# SPO2_New.net
KiCad netlist of a schematic drawn in EAGLE
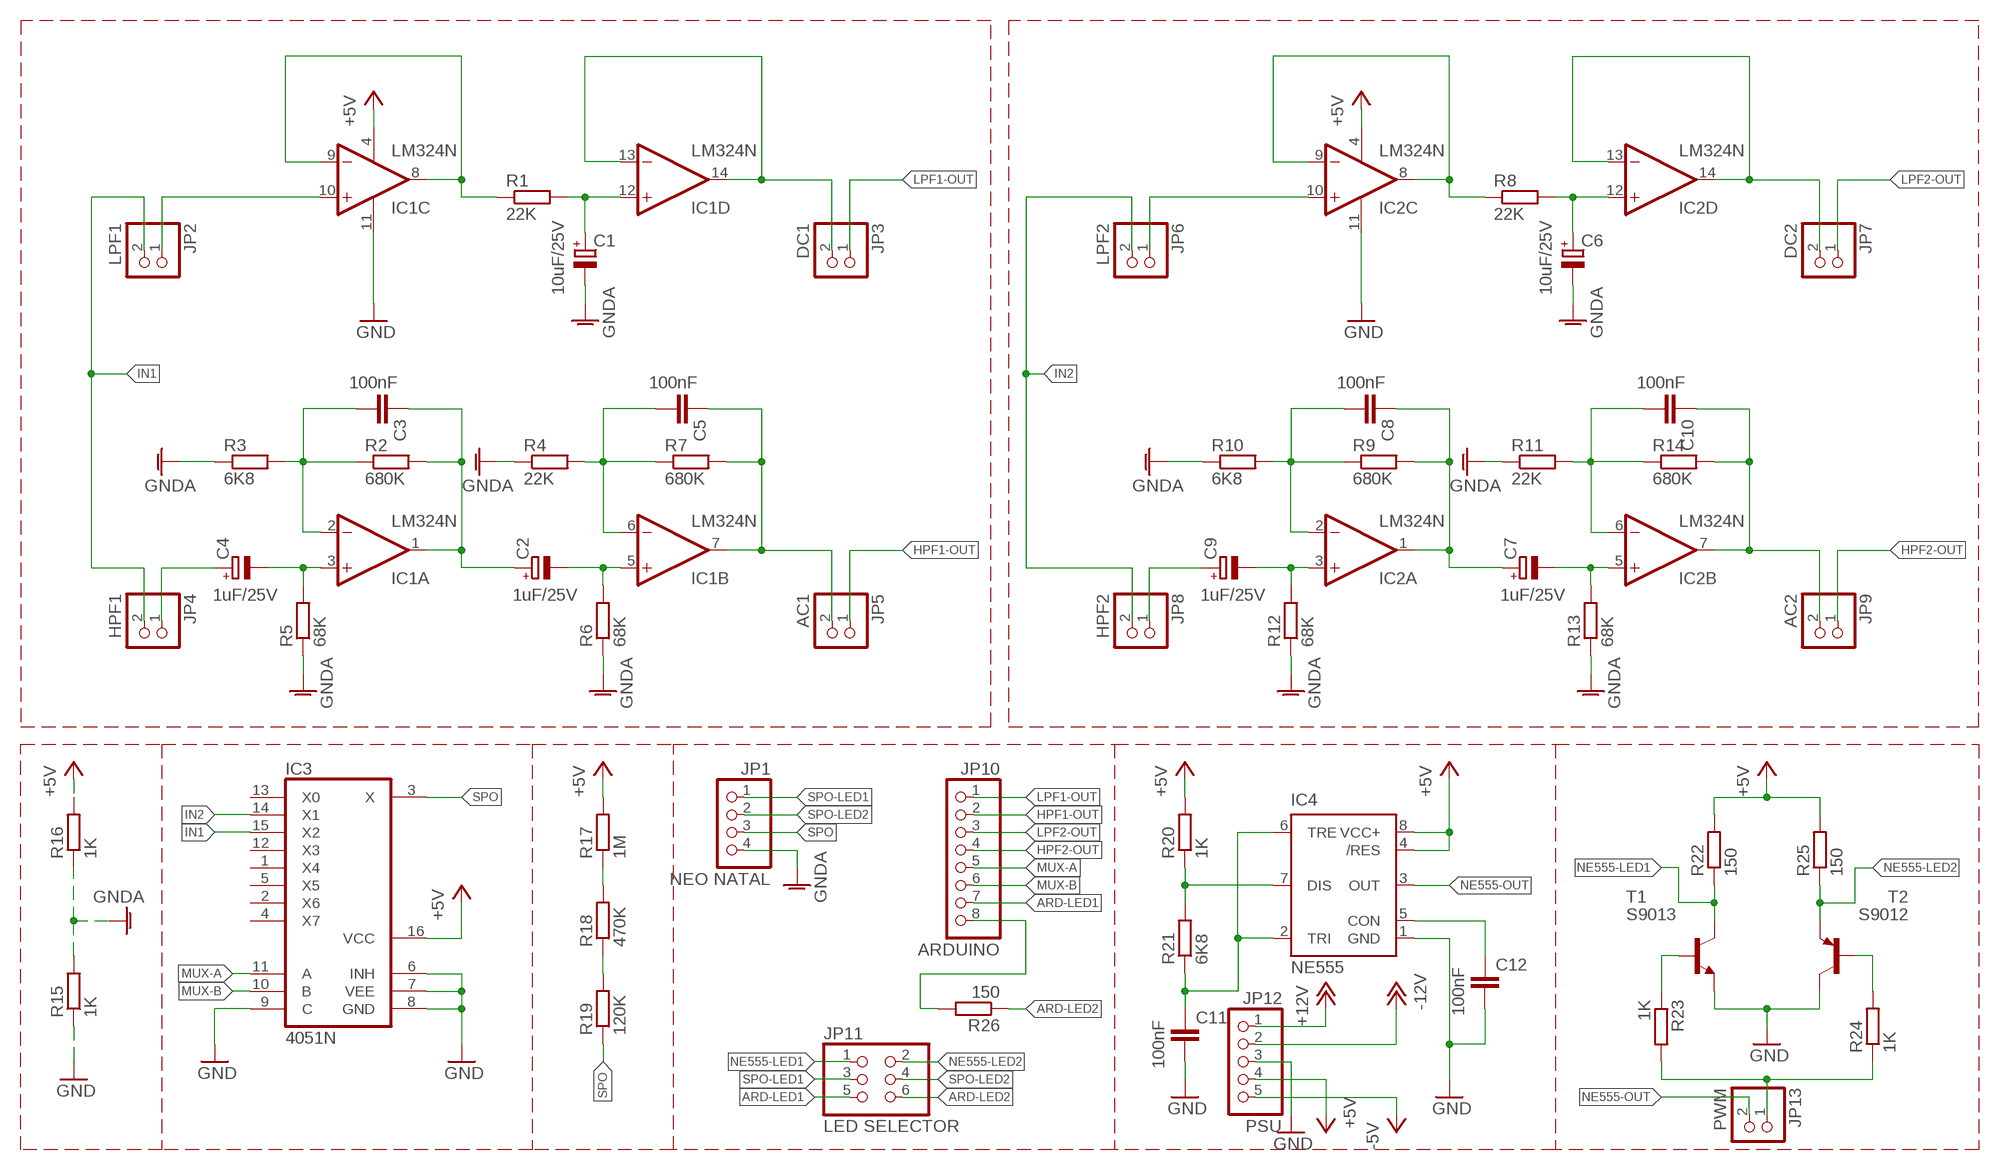
[diagram p0: schematic, sheet 1]

(export (version "E")
  (design (tool "Eeschema 10.0.6"))
  (components
    (comp (ref "C1")
      (value "10uF/25V")
      (footprint "eagle-import:E2,5-6")
      (libsource (lib "eagle-import") (part "CPOL-EUE2.5-6"))
    )
    (comp (ref "C2")
      (value "1uF/25V")
      (footprint "eagle-import:E2,5-6")
      (libsource (lib "eagle-import") (part "CPOL-EUE2.5-6"))
    )
    (comp (ref "C3")
      (value "100nF")
      (footprint "eagle-import:C050-025X075")
      (libsource (lib "eagle-import") (part "C-EU050-025X075"))
    )
    (comp (ref "C4")
      (value "1uF/25V")
      (footprint "eagle-import:E2,5-6")
      (libsource (lib "eagle-import") (part "CPOL-EUE2.5-6"))
    )
    (comp (ref "C5")
      (value "100nF")
      (footprint "eagle-import:C050-025X075")
      (libsource (lib "eagle-import") (part "C-EU050-025X075"))
    )
    (comp (ref "C6")
      (value "10uF/25V")
      (footprint "eagle-import:E2,5-6")
      (libsource (lib "eagle-import") (part "CPOL-EUE2.5-6"))
    )
    (comp (ref "C7")
      (value "1uF/25V")
      (footprint "eagle-import:E2,5-6")
      (libsource (lib "eagle-import") (part "CPOL-EUE2.5-6"))
    )
    (comp (ref "C8")
      (value "100nF")
      (footprint "eagle-import:C050-025X075")
      (libsource (lib "eagle-import") (part "C-EU050-025X075"))
    )
    (comp (ref "C9")
      (value "1uF/25V")
      (footprint "eagle-import:E2,5-6")
      (libsource (lib "eagle-import") (part "CPOL-EUE2.5-6"))
    )
    (comp (ref "C10")
      (value "100nF")
      (footprint "eagle-import:C050-025X075")
      (libsource (lib "eagle-import") (part "C-EU050-025X075"))
    )
    (comp (ref "C11")
      (value "100nF")
      (footprint "eagle-import:C050-025X075")
      (libsource (lib "eagle-import") (part "C-EU050-025X075"))
    )
    (comp (ref "C12")
      (value "100nF")
      (footprint "eagle-import:C050-025X075")
      (libsource (lib "eagle-import") (part "C-EU050-025X075"))
    )
    (comp (ref "IC1")
      (value "LM324N")
      (footprint "eagle-import:DIL14")
      (libsource (lib "eagle-import") (part "LM324N"))
    )
    (comp (ref "IC2")
      (value "LM324N")
      (footprint "eagle-import:DIL14")
      (libsource (lib "eagle-import") (part "LM324N"))
    )
    (comp (ref "IC3")
      (value "4051N")
      (footprint "eagle-import:DIL16")
      (libsource (lib "eagle-import") (part "4051N"))
    )
    (comp (ref "IC4")
      (value "NE555")
      (footprint "eagle-import:DIL-08")
      (fields (field (name "MF") "Arrow Electronics") (field (name "MPN") "NE555N"))
      (libsource (lib "eagle-import") (part "NE555"))
    )
    (comp (ref "JP1")
      (value "NEO NATAL")
      (footprint "eagle-import:1X04")
      (libsource (lib "eagle-import") (part "PINHD-1X4"))
    )
    (comp (ref "JP2")
      (value "LPF1")
      (footprint "eagle-import:1X02")
      (libsource (lib "eagle-import") (part "PINHD-1X2"))
    )
    (comp (ref "JP3")
      (value "DC1")
      (footprint "eagle-import:1X02")
      (libsource (lib "eagle-import") (part "PINHD-1X2"))
    )
    (comp (ref "JP4")
      (value "HPF1")
      (footprint "eagle-import:1X02")
      (libsource (lib "eagle-import") (part "PINHD-1X2"))
    )
    (comp (ref "JP5")
      (value "AC1")
      (footprint "eagle-import:1X02")
      (libsource (lib "eagle-import") (part "PINHD-1X2"))
    )
    (comp (ref "JP6")
      (value "LPF2")
      (footprint "eagle-import:1X02")
      (libsource (lib "eagle-import") (part "PINHD-1X2"))
    )
    (comp (ref "JP7")
      (value "DC2")
      (footprint "eagle-import:1X02")
      (libsource (lib "eagle-import") (part "PINHD-1X2"))
    )
    (comp (ref "JP8")
      (value "HPF2")
      (footprint "eagle-import:1X02")
      (libsource (lib "eagle-import") (part "PINHD-1X2"))
    )
    (comp (ref "JP9")
      (value "AC2")
      (footprint "eagle-import:1X02")
      (libsource (lib "eagle-import") (part "PINHD-1X2"))
    )
    (comp (ref "JP10")
      (value "ARDUINO")
      (footprint "eagle-import:1X08")
      (libsource (lib "eagle-import") (part "PINHD-1X8"))
    )
    (comp (ref "JP11")
      (value "LED SELECTOR")
      (footprint "eagle-import:2X03")
      (libsource (lib "eagle-import") (part "PINHD-2X3"))
    )
    (comp (ref "JP12")
      (value "PSU")
      (footprint "eagle-import:1X05")
      (libsource (lib "eagle-import") (part "PINHD-1X5{dblquote}"))
    )
    (comp (ref "JP13")
      (value "PWM")
      (footprint "eagle-import:1X02")
      (libsource (lib "eagle-import") (part "PINHD-1X2"))
    )
    (comp (ref "R1")
      (value "22K")
      (footprint "eagle-import:0207_7")
      (libsource (lib "eagle-import") (part "R-EU_0207/7"))
    )
    (comp (ref "R2")
      (value "680K")
      (footprint "eagle-import:0207_7")
      (libsource (lib "eagle-import") (part "R-EU_0207/7"))
    )
    (comp (ref "R3")
      (value "6K8")
      (footprint "eagle-import:0207_7")
      (libsource (lib "eagle-import") (part "R-EU_0207/7"))
    )
    (comp (ref "R4")
      (value "22K")
      (footprint "eagle-import:0207_7")
      (libsource (lib "eagle-import") (part "R-EU_0207/7"))
    )
    (comp (ref "R5")
      (value "68K")
      (footprint "eagle-import:0207_7")
      (libsource (lib "eagle-import") (part "R-EU_0207/7"))
    )
    (comp (ref "R6")
      (value "68K")
      (footprint "eagle-import:0207_7")
      (libsource (lib "eagle-import") (part "R-EU_0207/7"))
    )
    (comp (ref "R7")
      (value "680K")
      (footprint "eagle-import:0207_7")
      (libsource (lib "eagle-import") (part "R-EU_0207/7"))
    )
    (comp (ref "R8")
      (value "22K")
      (footprint "eagle-import:0207_7")
      (libsource (lib "eagle-import") (part "R-EU_0207/7"))
    )
    (comp (ref "R9")
      (value "680K")
      (footprint "eagle-import:0207_7")
      (libsource (lib "eagle-import") (part "R-EU_0207/7"))
    )
    (comp (ref "R10")
      (value "6K8")
      (footprint "eagle-import:0207_7")
      (libsource (lib "eagle-import") (part "R-EU_0207/7"))
    )
    (comp (ref "R11")
      (value "22K")
      (footprint "eagle-import:0207_7")
      (libsource (lib "eagle-import") (part "R-EU_0207/7"))
    )
    (comp (ref "R12")
      (value "68K")
      (footprint "eagle-import:0207_7")
      (libsource (lib "eagle-import") (part "R-EU_0207/7"))
    )
    (comp (ref "R13")
      (value "68K")
      (footprint "eagle-import:0207_7")
      (libsource (lib "eagle-import") (part "R-EU_0207/7"))
    )
    (comp (ref "R14")
      (value "680K")
      (footprint "eagle-import:0207_7")
      (libsource (lib "eagle-import") (part "R-EU_0207/7"))
    )
    (comp (ref "R15")
      (value "1K")
      (footprint "eagle-import:0207_7")
      (libsource (lib "eagle-import") (part "R-EU_0207/7"))
    )
    (comp (ref "R16")
      (value "1K")
      (footprint "eagle-import:0207_7")
      (libsource (lib "eagle-import") (part "R-EU_0207/7"))
    )
    (comp (ref "R17")
      (value "1M")
      (footprint "eagle-import:0207_7")
      (libsource (lib "eagle-import") (part "R-EU_0207/7"))
    )
    (comp (ref "R18")
      (value "470K")
      (footprint "eagle-import:0207_7")
      (libsource (lib "eagle-import") (part "R-EU_0207/7"))
    )
    (comp (ref "R19")
      (value "120K")
      (footprint "eagle-import:0207_7")
      (libsource (lib "eagle-import") (part "R-EU_0207/7"))
    )
    (comp (ref "R20")
      (value "1K")
      (footprint "eagle-import:0207_7")
      (libsource (lib "eagle-import") (part "R-EU_0207/7"))
    )
    (comp (ref "R21")
      (value "6K8")
      (footprint "eagle-import:0207_7")
      (libsource (lib "eagle-import") (part "R-EU_0207/7"))
    )
    (comp (ref "R22")
      (value "150")
      (footprint "eagle-import:0207_7")
      (libsource (lib "eagle-import") (part "R-EU_0207/7"))
    )
    (comp (ref "R23")
      (value "1K")
      (footprint "eagle-import:0207_7")
      (libsource (lib "eagle-import") (part "R-EU_0207/7"))
    )
    (comp (ref "R24")
      (value "1K")
      (footprint "eagle-import:0207_7")
      (libsource (lib "eagle-import") (part "R-EU_0207/7"))
    )
    (comp (ref "R25")
      (value "150")
      (footprint "eagle-import:0207_7")
      (libsource (lib "eagle-import") (part "R-EU_0207/7"))
    )
    (comp (ref "R26")
      (value "150")
      (footprint "eagle-import:0207_7")
      (libsource (lib "eagle-import") (part "R-EU_0207/7"))
    )
    (comp (ref "T1")
      (value "S9013")
      (footprint "eagle-import:TO92-EBC")
      (libsource (lib "eagle-import") (part "-NPN-TO92-EBCBC319"))
    )
    (comp (ref "T2")
      (value "S9012")
      (footprint "eagle-import:TO92-EBC")
      (libsource (lib "eagle-import") (part "-PNP-TO92-EBCBC327-16"))
    )
  )
  (nets
    (net (code "1") (name "+5V") (class "Default")
      (node (ref "IC1") (pin "4") (pinfunction "V+_4") (pintype "power_in"))
      (node (ref "IC2") (pin "4") (pinfunction "V+_4") (pintype "power_in"))
      (node (ref "IC3") (pin "16") (pinfunction "VCC_16") (pintype "power_in"))
      (node (ref "IC4") (pin "4") (pinfunction "/RES_4") (pintype "input"))
      (node (ref "IC4") (pin "8") (pinfunction "VCC+_8") (pintype "power_in"))
      (node (ref "JP12") (pin "4") (pinfunction "4_4") (pintype "passive"))
      (node (ref "R16") (pin "2") (pinfunction "2_2") (pintype "passive"))
      (node (ref "R17") (pin "2") (pinfunction "2_2") (pintype "passive"))
      (node (ref "R20") (pin "2") (pinfunction "2_2") (pintype "passive"))
      (node (ref "R22") (pin "2") (pinfunction "2_2") (pintype "passive"))
      (node (ref "R25") (pin "2") (pinfunction "2_2") (pintype "passive"))
    )
    (net (code "2") (name "+12V") (class "Default")
      (node (ref "JP12") (pin "1") (pinfunction "1_1") (pintype "passive"))
    )
    (net (code "3") (name "-5V") (class "Default")
      (node (ref "JP12") (pin "5") (pinfunction "5_5") (pintype "passive"))
    )
    (net (code "4") (name "-12V") (class "Default")
      (node (ref "JP12") (pin "2") (pinfunction "2_2") (pintype "passive"))
    )
    (net (code "5") (name "ARD-LED1") (class "Default")
      (node (ref "JP10") (pin "7") (pinfunction "7_7") (pintype "passive"))
      (node (ref "JP11") (pin "5") (pinfunction "5_5") (pintype "passive"))
    )
    (net (code "6") (name "ARD-LED2") (class "Default")
      (node (ref "JP11") (pin "6") (pinfunction "6_6") (pintype "passive"))
      (node (ref "R26") (pin "1") (pinfunction "1_1") (pintype "passive"))
    )
    (net (code "7") (name "GND") (class "Default")
      (node (ref "C11") (pin "2") (pinfunction "2_2") (pintype "passive"))
      (node (ref "C12") (pin "2") (pinfunction "2_2") (pintype "passive"))
      (node (ref "IC1") (pin "11") (pinfunction "V-_11") (pintype "power_in"))
      (node (ref "IC2") (pin "11") (pinfunction "V-_11") (pintype "power_in"))
      (node (ref "IC3") (pin "6") (pinfunction "INH_6") (pintype "input"))
      (node (ref "IC3") (pin "7") (pinfunction "VEE_7") (pintype "power_in"))
      (node (ref "IC3") (pin "8") (pinfunction "GND_8") (pintype "power_in"))
      (node (ref "IC3") (pin "9") (pinfunction "C_9") (pintype "input"))
      (node (ref "IC4") (pin "1") (pinfunction "GND_1") (pintype "power_in"))
      (node (ref "JP12") (pin "3") (pinfunction "3_3") (pintype "passive"))
      (node (ref "R15") (pin "1") (pinfunction "1_1") (pintype "passive"))
      (node (ref "T1") (pin "E") (pinfunction "E_E") (pintype "passive"))
      (node (ref "T2") (pin "C") (pinfunction "C_C") (pintype "passive"))
    )
    (net (code "8") (name "GNDA") (class "Default")
      (node (ref "C1") (pin "-") (pinfunction "-_-") (pintype "passive"))
      (node (ref "C6") (pin "-") (pinfunction "-_-") (pintype "passive"))
      (node (ref "JP1") (pin "4") (pinfunction "4_4") (pintype "passive"))
      (node (ref "R10") (pin "1") (pinfunction "1_1") (pintype "passive"))
      (node (ref "R11") (pin "1") (pinfunction "1_1") (pintype "passive"))
      (node (ref "R12") (pin "1") (pinfunction "1_1") (pintype "passive"))
      (node (ref "R13") (pin "1") (pinfunction "1_1") (pintype "passive"))
      (node (ref "R15") (pin "2") (pinfunction "2_2") (pintype "passive"))
      (node (ref "R16") (pin "1") (pinfunction "1_1") (pintype "passive"))
      (node (ref "R3") (pin "1") (pinfunction "1_1") (pintype "passive"))
      (node (ref "R4") (pin "1") (pinfunction "1_1") (pintype "passive"))
      (node (ref "R5") (pin "1") (pinfunction "1_1") (pintype "passive"))
      (node (ref "R6") (pin "1") (pinfunction "1_1") (pintype "passive"))
    )
    (net (code "9") (name "HPF1-OUT") (class "Default")
      (node (ref "JP10") (pin "2") (pinfunction "2_2") (pintype "passive"))
      (node (ref "JP5") (pin "1") (pinfunction "1_1") (pintype "passive"))
    )
    (net (code "10") (name "HPF2-OUT") (class "Default")
      (node (ref "JP10") (pin "4") (pinfunction "4_4") (pintype "passive"))
      (node (ref "JP9") (pin "1") (pinfunction "1_1") (pintype "passive"))
    )
    (net (code "11") (name "IN1") (class "Default")
      (node (ref "IC3") (pin "15") (pinfunction "X2_15") (pintype "bidirectional"))
      (node (ref "JP2") (pin "2") (pinfunction "2_2") (pintype "passive"))
      (node (ref "JP4") (pin "2") (pinfunction "2_2") (pintype "passive"))
    )
    (net (code "12") (name "IN2") (class "Default")
      (node (ref "IC3") (pin "14") (pinfunction "X1_14") (pintype "bidirectional"))
      (node (ref "JP6") (pin "2") (pinfunction "2_2") (pintype "passive"))
      (node (ref "JP8") (pin "2") (pinfunction "2_2") (pintype "passive"))
    )
    (net (code "13") (name "LPF1-OUT") (class "Default")
      (node (ref "JP10") (pin "1") (pinfunction "1_1") (pintype "passive"))
      (node (ref "JP3") (pin "1") (pinfunction "1_1") (pintype "passive"))
    )
    (net (code "14") (name "LPF2-OUT") (class "Default")
      (node (ref "JP10") (pin "3") (pinfunction "3_3") (pintype "passive"))
      (node (ref "JP7") (pin "1") (pinfunction "1_1") (pintype "passive"))
    )
    (net (code "15") (name "MUX-A") (class "Default")
      (node (ref "IC3") (pin "11") (pinfunction "A_11") (pintype "input"))
      (node (ref "JP10") (pin "5") (pinfunction "5_5") (pintype "passive"))
    )
    (net (code "16") (name "MUX-B") (class "Default")
      (node (ref "IC3") (pin "10") (pinfunction "B_10") (pintype "input"))
      (node (ref "JP10") (pin "6") (pinfunction "6_6") (pintype "passive"))
    )
    (net (code "17") (name "NE555-LED1") (class "Default")
      (node (ref "JP11") (pin "1") (pinfunction "1_1") (pintype "passive"))
      (node (ref "R22") (pin "1") (pinfunction "1_1") (pintype "passive"))
      (node (ref "T1") (pin "C") (pinfunction "C_C") (pintype "passive"))
    )
    (net (code "18") (name "NE555-LED2") (class "Default")
      (node (ref "JP11") (pin "2") (pinfunction "2_2") (pintype "passive"))
      (node (ref "R25") (pin "1") (pinfunction "1_1") (pintype "passive"))
      (node (ref "T2") (pin "E") (pinfunction "E_E") (pintype "passive"))
    )
    (net (code "19") (name "NE555-OUT") (class "Default")
      (node (ref "IC4") (pin "3") (pinfunction "OUT_3") (pintype "output"))
      (node (ref "JP13") (pin "2") (pinfunction "2_2") (pintype "passive"))
    )
    (net (code "20") (name "Net-(C4-Pad+)") (class "Default")
      (node (ref "C4") (pin "+") (pinfunction "+_+") (pintype "passive"))
      (node (ref "JP4") (pin "1") (pinfunction "1_1") (pintype "passive"))
    )
    (net (code "21") (name "Net-(C9-Pad+)") (class "Default")
      (node (ref "C9") (pin "+") (pinfunction "+_+") (pintype "passive"))
      (node (ref "JP8") (pin "1") (pinfunction "1_1") (pintype "passive"))
    )
    (net (code "22") (name "Net-(IC1A-+IN)") (class "Default")
      (node (ref "C4") (pin "-") (pinfunction "-_-") (pintype "passive"))
      (node (ref "IC1") (pin "3") (pinfunction "+IN_3") (pintype "input"))
      (node (ref "R5") (pin "2") (pinfunction "2_2") (pintype "passive"))
    )
    (net (code "23") (name "Net-(IC1A--IN)") (class "Default")
      (node (ref "C3") (pin "2") (pinfunction "2_2") (pintype "passive"))
      (node (ref "IC1") (pin "2") (pinfunction "-IN_2") (pintype "input"))
      (node (ref "R2") (pin "1") (pinfunction "1_1") (pintype "passive"))
      (node (ref "R3") (pin "2") (pinfunction "2_2") (pintype "passive"))
    )
    (net (code "24") (name "Net-(IC1A-OUT)") (class "Default")
      (node (ref "C2") (pin "+") (pinfunction "+_+") (pintype "passive"))
      (node (ref "C3") (pin "1") (pinfunction "1_1") (pintype "passive"))
      (node (ref "IC1") (pin "1") (pinfunction "OUT_1") (pintype "output"))
      (node (ref "R2") (pin "2") (pinfunction "2_2") (pintype "passive"))
    )
    (net (code "25") (name "Net-(IC1B-+IN)") (class "Default")
      (node (ref "C2") (pin "-") (pinfunction "-_-") (pintype "passive"))
      (node (ref "IC1") (pin "5") (pinfunction "+IN_5") (pintype "input"))
      (node (ref "R6") (pin "2") (pinfunction "2_2") (pintype "passive"))
    )
    (net (code "26") (name "Net-(IC1B--IN)") (class "Default")
      (node (ref "C5") (pin "2") (pinfunction "2_2") (pintype "passive"))
      (node (ref "IC1") (pin "6") (pinfunction "-IN_6") (pintype "input"))
      (node (ref "R4") (pin "2") (pinfunction "2_2") (pintype "passive"))
      (node (ref "R7") (pin "1") (pinfunction "1_1") (pintype "passive"))
    )
    (net (code "27") (name "Net-(IC1B-OUT)") (class "Default")
      (node (ref "C5") (pin "1") (pinfunction "1_1") (pintype "passive"))
      (node (ref "IC1") (pin "7") (pinfunction "OUT_7") (pintype "output"))
      (node (ref "JP5") (pin "2") (pinfunction "2_2") (pintype "passive"))
      (node (ref "R7") (pin "2") (pinfunction "2_2") (pintype "passive"))
    )
    (net (code "28") (name "Net-(IC1C-+IN)") (class "Default")
      (node (ref "IC1") (pin "10") (pinfunction "+IN_10") (pintype "input"))
      (node (ref "JP2") (pin "1") (pinfunction "1_1") (pintype "passive"))
    )
    (net (code "29") (name "Net-(IC1C--IN)") (class "Default")
      (node (ref "IC1") (pin "8") (pinfunction "OUT_8") (pintype "output"))
      (node (ref "IC1") (pin "9") (pinfunction "-IN_9") (pintype "input"))
      (node (ref "R1") (pin "1") (pinfunction "1_1") (pintype "passive"))
    )
    (net (code "30") (name "Net-(IC1D-+IN)") (class "Default")
      (node (ref "C1") (pin "+") (pinfunction "+_+") (pintype "passive"))
      (node (ref "IC1") (pin "12") (pinfunction "+IN_12") (pintype "input"))
      (node (ref "R1") (pin "2") (pinfunction "2_2") (pintype "passive"))
    )
    (net (code "31") (name "Net-(IC1D--IN)") (class "Default")
      (node (ref "IC1") (pin "13") (pinfunction "-IN_13") (pintype "input"))
      (node (ref "IC1") (pin "14") (pinfunction "OUT_14") (pintype "output"))
      (node (ref "JP3") (pin "2") (pinfunction "2_2") (pintype "passive"))
    )
    (net (code "32") (name "Net-(IC2A-+IN)") (class "Default")
      (node (ref "C9") (pin "-") (pinfunction "-_-") (pintype "passive"))
      (node (ref "IC2") (pin "3") (pinfunction "+IN_3") (pintype "input"))
      (node (ref "R12") (pin "2") (pinfunction "2_2") (pintype "passive"))
    )
    (net (code "33") (name "Net-(IC2A--IN)") (class "Default")
      (node (ref "C8") (pin "2") (pinfunction "2_2") (pintype "passive"))
      (node (ref "IC2") (pin "2") (pinfunction "-IN_2") (pintype "input"))
      (node (ref "R10") (pin "2") (pinfunction "2_2") (pintype "passive"))
      (node (ref "R9") (pin "1") (pinfunction "1_1") (pintype "passive"))
    )
    (net (code "34") (name "Net-(IC2A-OUT)") (class "Default")
      (node (ref "C7") (pin "+") (pinfunction "+_+") (pintype "passive"))
      (node (ref "C8") (pin "1") (pinfunction "1_1") (pintype "passive"))
      (node (ref "IC2") (pin "1") (pinfunction "OUT_1") (pintype "output"))
      (node (ref "R9") (pin "2") (pinfunction "2_2") (pintype "passive"))
    )
    (net (code "35") (name "Net-(IC2B-+IN)") (class "Default")
      (node (ref "C7") (pin "-") (pinfunction "-_-") (pintype "passive"))
      (node (ref "IC2") (pin "5") (pinfunction "+IN_5") (pintype "input"))
      (node (ref "R13") (pin "2") (pinfunction "2_2") (pintype "passive"))
    )
    (net (code "36") (name "Net-(IC2B--IN)") (class "Default")
      (node (ref "C10") (pin "2") (pinfunction "2_2") (pintype "passive"))
      (node (ref "IC2") (pin "6") (pinfunction "-IN_6") (pintype "input"))
      (node (ref "R11") (pin "2") (pinfunction "2_2") (pintype "passive"))
      (node (ref "R14") (pin "1") (pinfunction "1_1") (pintype "passive"))
    )
    (net (code "37") (name "Net-(IC2B-OUT)") (class "Default")
      (node (ref "C10") (pin "1") (pinfunction "1_1") (pintype "passive"))
      (node (ref "IC2") (pin "7") (pinfunction "OUT_7") (pintype "output"))
      (node (ref "JP9") (pin "2") (pinfunction "2_2") (pintype "passive"))
      (node (ref "R14") (pin "2") (pinfunction "2_2") (pintype "passive"))
    )
    (net (code "38") (name "Net-(IC2C-+IN)") (class "Default")
      (node (ref "IC2") (pin "10") (pinfunction "+IN_10") (pintype "input"))
      (node (ref "JP6") (pin "1") (pinfunction "1_1") (pintype "passive"))
    )
    (net (code "39") (name "Net-(IC2C--IN)") (class "Default")
      (node (ref "IC2") (pin "8") (pinfunction "OUT_8") (pintype "output"))
      (node (ref "IC2") (pin "9") (pinfunction "-IN_9") (pintype "input"))
      (node (ref "R8") (pin "1") (pinfunction "1_1") (pintype "passive"))
    )
    (net (code "40") (name "Net-(IC2D-+IN)") (class "Default")
      (node (ref "C6") (pin "+") (pinfunction "+_+") (pintype "passive"))
      (node (ref "IC2") (pin "12") (pinfunction "+IN_12") (pintype "input"))
      (node (ref "R8") (pin "2") (pinfunction "2_2") (pintype "passive"))
    )
    (net (code "41") (name "Net-(IC2D--IN)") (class "Default")
      (node (ref "IC2") (pin "13") (pinfunction "-IN_13") (pintype "input"))
      (node (ref "IC2") (pin "14") (pinfunction "OUT_14") (pintype "output"))
      (node (ref "JP7") (pin "2") (pinfunction "2_2") (pintype "passive"))
    )
    (net (code "42") (name "Net-(IC4-CON)") (class "Default")
      (node (ref "C12") (pin "1") (pinfunction "1_1") (pintype "passive"))
      (node (ref "IC4") (pin "5") (pinfunction "CON_5") (pintype "input"))
    )
    (net (code "43") (name "Net-(IC4-DIS)") (class "Default")
      (node (ref "IC4") (pin "7") (pinfunction "DIS_7") (pintype "input"))
      (node (ref "R20") (pin "1") (pinfunction "1_1") (pintype "passive"))
      (node (ref "R21") (pin "2") (pinfunction "2_2") (pintype "passive"))
    )
    (net (code "44") (name "Net-(IC4-TRE)") (class "Default")
      (node (ref "C11") (pin "1") (pinfunction "1_1") (pintype "passive"))
      (node (ref "IC4") (pin "2") (pinfunction "TRI_2") (pintype "input"))
      (node (ref "IC4") (pin "6") (pinfunction "TRE_6") (pintype "input"))
      (node (ref "R21") (pin "1") (pinfunction "1_1") (pintype "passive"))
    )
    (net (code "45") (name "Net-(JP10-Pad8)") (class "Default")
      (node (ref "JP10") (pin "8") (pinfunction "8_8") (pintype "passive"))
      (node (ref "R26") (pin "2") (pinfunction "2_2") (pintype "passive"))
    )
    (net (code "46") (name "Net-(JP13-Pad1)") (class "Default")
      (node (ref "JP13") (pin "1") (pinfunction "1_1") (pintype "passive"))
      (node (ref "R23") (pin "2") (pinfunction "2_2") (pintype "passive"))
      (node (ref "R24") (pin "1") (pinfunction "1_1") (pintype "passive"))
    )
    (net (code "47") (name "Net-(R17-Pad1)") (class "Default")
      (node (ref "R17") (pin "1") (pinfunction "1_1") (pintype "passive"))
      (node (ref "R18") (pin "2") (pinfunction "2_2") (pintype "passive"))
    )
    (net (code "48") (name "Net-(R18-Pad1)") (class "Default")
      (node (ref "R18") (pin "1") (pinfunction "1_1") (pintype "passive"))
      (node (ref "R19") (pin "2") (pinfunction "2_2") (pintype "passive"))
    )
    (net (code "49") (name "Net-(R23-Pad1)") (class "Default")
      (node (ref "R23") (pin "1") (pinfunction "1_1") (pintype "passive"))
      (node (ref "T1") (pin "B") (pinfunction "B_B") (pintype "passive"))
    )
    (net (code "50") (name "Net-(R24-Pad2)") (class "Default")
      (node (ref "R24") (pin "2") (pinfunction "2_2") (pintype "passive"))
      (node (ref "T2") (pin "B") (pinfunction "B_B") (pintype "passive"))
    )
    (net (code "51") (name "SPO") (class "Default")
      (node (ref "IC3") (pin "3") (pinfunction "X_3") (pintype "bidirectional"))
      (node (ref "JP1") (pin "3") (pinfunction "3_3") (pintype "passive"))
      (node (ref "R19") (pin "1") (pinfunction "1_1") (pintype "passive"))
    )
    (net (code "52") (name "SPO-LED1") (class "Default")
      (node (ref "JP1") (pin "1") (pinfunction "1_1") (pintype "passive"))
      (node (ref "JP11") (pin "3") (pinfunction "3_3") (pintype "passive"))
    )
    (net (code "53") (name "SPO-LED2") (class "Default")
      (node (ref "JP1") (pin "2") (pinfunction "2_2") (pintype "passive"))
      (node (ref "JP11") (pin "4") (pinfunction "4_4") (pintype "passive"))
    )
    (net (code "54") (name "unconnected-(IC3-X0-Pad13)") (class "Default")
      (node (ref "IC3") (pin "13") (pinfunction "X0_13") (pintype "bidirectional"))
    )
    (net (code "55") (name "unconnected-(IC3-X3-Pad12)") (class "Default")
      (node (ref "IC3") (pin "12") (pinfunction "X3_12") (pintype "bidirectional"))
    )
    (net (code "56") (name "unconnected-(IC3-X4-Pad1)") (class "Default")
      (node (ref "IC3") (pin "1") (pinfunction "X4_1") (pintype "bidirectional"))
    )
    (net (code "57") (name "unconnected-(IC3-X5-Pad5)") (class "Default")
      (node (ref "IC3") (pin "5") (pinfunction "X5_5") (pintype "bidirectional"))
    )
    (net (code "58") (name "unconnected-(IC3-X6-Pad2)") (class "Default")
      (node (ref "IC3") (pin "2") (pinfunction "X6_2") (pintype "bidirectional"))
    )
    (net (code "59") (name "unconnected-(IC3-X7-Pad4)") (class "Default")
      (node (ref "IC3") (pin "4") (pinfunction "X7_4") (pintype "bidirectional"))
    )
  )
)
